# Sheet1.net
KiCad netlist of a schematic drawn in Altium Designer
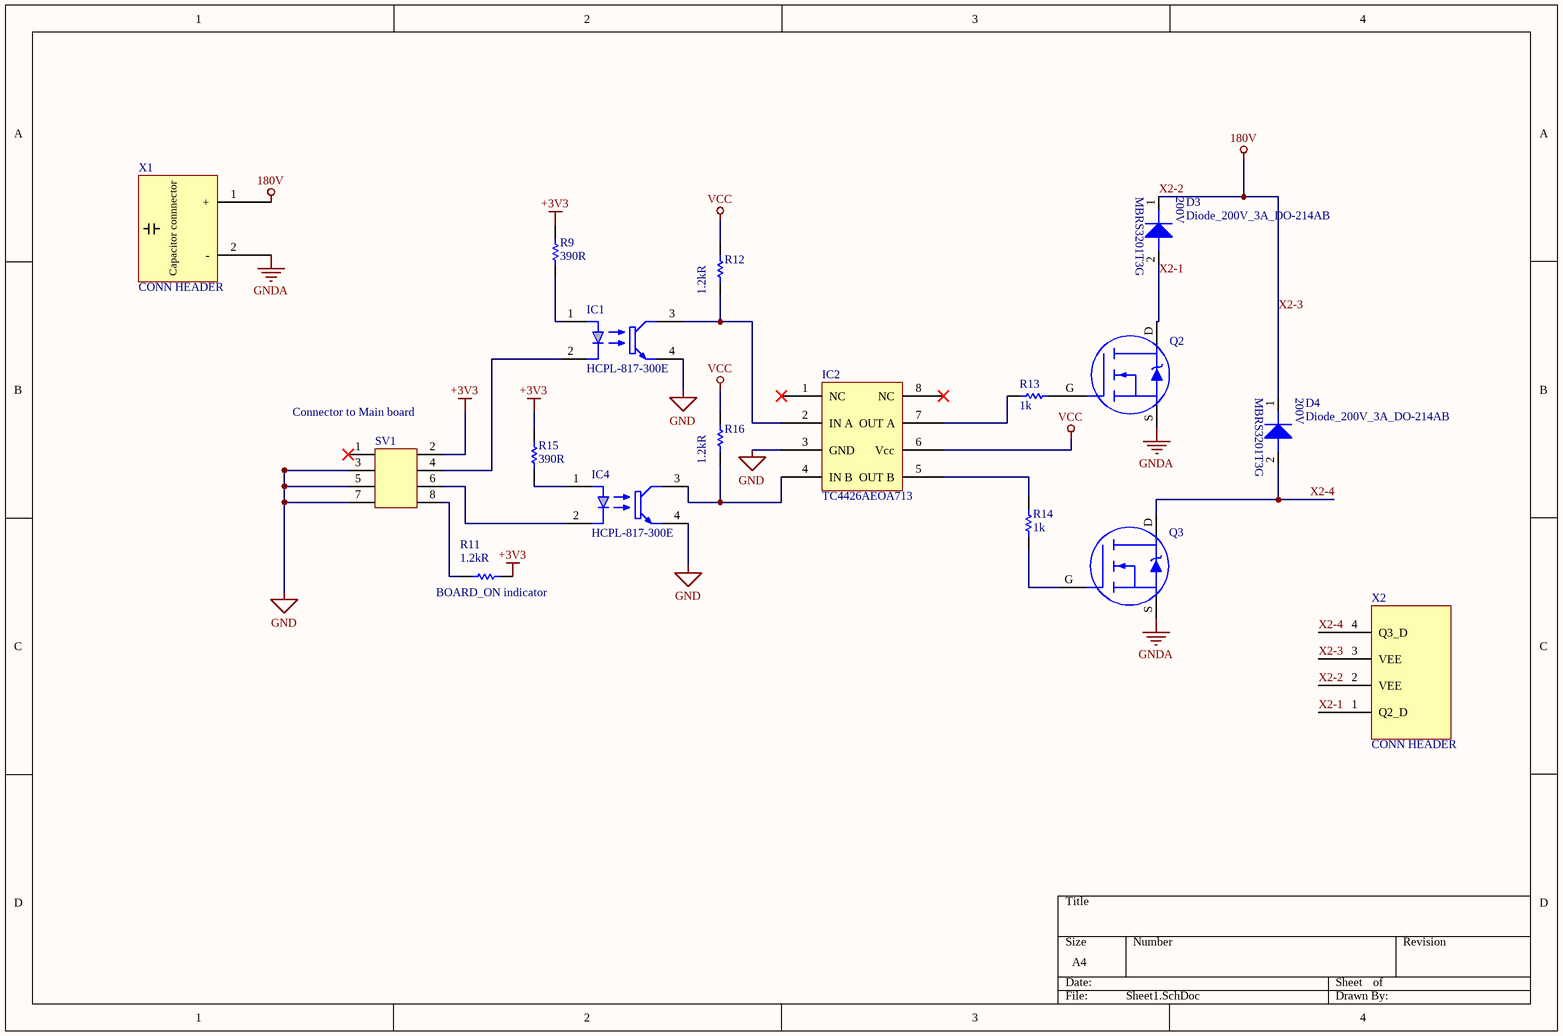
[diagram p0: Sheet1.SchDoc]

(export (version "E")
  (design (tool "Eeschema 10.0.6"))
  (components
    (comp (ref "D3")
      (value "Diode_200V_3A_DO-214AB")
      (footprint "D320")
      (fields
        (field (name "MANUFACTURER") "ON Semiconductor")
        (field (name "MANUFACTURER PART NUMBER") "MBRS3201T3G")
      )
      (libsource (lib "Schlib1") (part "Diode_200V_3A_DO-214AB"))
    )
    (comp (ref "D4")
      (value "Diode_200V_3A_DO-214AB")
      (footprint "D320")
      (fields
        (field (name "MANUFACTURER") "ON Semiconductor")
        (field (name "MANUFACTURER PART NUMBER") "MBRS3201T3G")
      )
      (libsource (lib "Schlib1") (part "Diode_200V_3A_DO-214AB"))
    )
    (comp (ref "IC1")
      (value "HCPL-817-300E")
      (footprint "OPTOISOLATOR_5KV_TRANSISTOR_4SMD")
      (description "OPTOISOLATOR 5KV TRANSISTOR 4SMD")
      (fields (field (name "MANUFACTURER") "Broadcom Avago"))
      (libsource (lib "Phototransistor(Optocoupler)") (part "HCPL-817-300E"))
    )
    (comp (ref "IC2")
      (value "TC4426AEOA713")
      (footprint "CI Driver")
      (description "MOSFET DRVR 1.5A 2-OUT Lo Side Inv 8-Pin SOIC N T/R")
      (fields (field (name "MANUFACTURER") "Microchip"))
      (libsource (lib "Drivers") (part "TC4426AEOA713"))
    )
    (comp (ref "IC4")
      (value "HCPL-817-300E")
      (footprint "OPTOISOLATOR_5KV_TRANSISTOR_4SMD")
      (description "OPTOISOLATOR 5KV TRANSISTOR 4SMD")
      (fields (field (name "MANUFACTURER") "Broadcom Avago"))
      (libsource (lib "Phototransistor(Optocoupler)") (part "HCPL-817-300E"))
    )
    (comp (ref "Q2")
      (value "IRFSL4127PBF")
      (footprint "TO-262")
      (description "200V Single N-Channel HEXFET Power MOSFET Switch in a TO-262 package")
      (fields (field (name "MANUFACTURER") "Infineon"))
      (libsource (lib "Transistors") (part "IRFSL4127PBF"))
    )
    (comp (ref "Q3")
      (value "IRFSL4127PBF")
      (footprint "TO-262")
      (description "200V Single N-Channel HEXFET Power MOSFET Switch in a TO-262 package")
      (fields (field (name "MANUFACTURER") "Infineon"))
      (libsource (lib "Transistors") (part "IRFSL4127PBF"))
    )
    (comp (ref "R9")
      (value "390R")
      (footprint "Resistor_0805")
      (description "RES SMD 0805 390R 5% 1/8W")
      (fields (field (name "TOLERANCE") "1%"))
      (libsource (lib "Resistors") (part "Res_390R_0805"))
    )
    (comp (ref "R11")
      (value "Res_1.2K_0805_1%")
      (footprint "0805")
      (description "PANASONIC ELECTRONIC COMPONENTS - ERJ6ENF1201V - RES, THICK FILM, 1K2, 125MW, 1%, REEL")
      (fields
        (field (name "MANUFACTURER") "Panasonic")
        (field (name "MANUFACTURER PART NUMBER") "ERJ-6ENF1201V")
      )
      (libsource (lib "Resistors") (part "Res_1.2K_0805_1%"))
    )
    (comp (ref "R12")
      (value "Res_1.2K_0805_1%")
      (footprint "0805")
      (description "PANASONIC ELECTRONIC COMPONENTS - ERJ6ENF1201V - RES, THICK FILM, 1K2, 125MW, 1%, REEL")
      (fields
        (field (name "MANUFACTURER") "Panasonic")
        (field (name "MANUFACTURER PART NUMBER") "ERJ-6ENF1201V")
      )
      (libsource (lib "Resistors") (part "Res_1.2K_0805_1%"))
    )
    (comp (ref "R13")
      (value "1k")
      (footprint "Resistor_0805")
      (description "RES SMD 0805 1k 1/8W")
      (libsource (lib "Resistors") (part "Res_1k_0805"))
    )
    (comp (ref "R14")
      (value "1k")
      (footprint "Resistor_0805")
      (description "RES SMD 0805 1k 1/8W")
      (libsource (lib "Resistors") (part "Res_1k_0805"))
    )
    (comp (ref "R15")
      (value "390R")
      (footprint "Resistor_0805")
      (description "RES SMD 0805 390R 5% 1/8W")
      (fields (field (name "TOLERANCE") "1%"))
      (libsource (lib "Resistors") (part "Res_390R_0805"))
    )
    (comp (ref "R16")
      (value "Res_1.2K_0805_1%")
      (footprint "0805")
      (description "PANASONIC ELECTRONIC COMPONENTS - ERJ6ENF1201V - RES, THICK FILM, 1K2, 125MW, 1%, REEL")
      (fields
        (field (name "MANUFACTURER") "Panasonic")
        (field (name "MANUFACTURER PART NUMBER") "ERJ-6ENF1201V")
      )
      (libsource (lib "Resistors") (part "Res_1.2K_0805_1%"))
    )
    (comp (ref "SV1")
      (value "90131-0764")
      (footprint "CONN HEADER VERT 8POS 2.54MM")
      (description "Conn Unshrouded Header HDR 8 POS 2.54mm Solder ST Thru-Hole Tray")
      (fields (field (name "MANUFACTURER") "Molex"))
      (libsource (lib "Conectors_Molex") (part "90131-0764"))
    )
    (comp (ref "X1")
      (value "CONN HEADER")
      (footprint "CONN HEADER R_A 2POS 3.98MM")
      (description "Conn Wire to Board HDR 2 POS 3.96mm Solder RA Thru-Hole KK® Bag")
      (libsource (lib "kicker_andrei") (part "CONN HEADER R_A 2POS 3.96MM"))
    )
    (comp (ref "X2")
      (value "CONN HEADER")
      (footprint "CONN HEADER R_A 4POS 3.98MM")
      (description "Headers & Wire Housings R/A PCB HDR 4P TIN FRICTION LOCK")
      (libsource (lib "kicker_andrei") (part "CONN HEADER R_A 4POS 3.96MM"))
    )
  )
  (nets
    (net (code "1") (name "+3V3") (class "Default")
      (node (ref "R11") (pin "2") (pinfunction "2_2") (pintype "passive"))
      (node (ref "R15") (pin "2") (pinfunction "2_2") (pintype "passive"))
      (node (ref "R9") (pin "2") (pinfunction "2_2") (pintype "passive"))
      (node (ref "SV1") (pin "2") (pinfunction "2_2") (pintype "passive"))
    )
    (net (code "2") (name "/X2-1") (class "Default")
      (node (ref "D3") (pin "2") (pinfunction "2_2") (pintype "passive"))
      (node (ref "Q2") (pin "D") (pinfunction "D_D") (pintype "passive"))
      (node (ref "X2") (pin "1") (pinfunction "Q2_D_1") (pintype "passive"))
    )
    (net (code "3") (name "/X2-4") (class "Default")
      (node (ref "D4") (pin "2") (pinfunction "2_2") (pintype "passive"))
      (node (ref "Q3") (pin "D") (pinfunction "D_D") (pintype "passive"))
      (node (ref "X2") (pin "4") (pinfunction "Q3_D_4") (pintype "passive"))
    )
    (net (code "4") (name "180V") (class "Default")
      (node (ref "D3") (pin "1") (pinfunction "1_1") (pintype "passive"))
      (node (ref "D4") (pin "1") (pinfunction "1_1") (pintype "passive"))
      (node (ref "X1") (pin "1") (pinfunction "+_1") (pintype "passive"))
      (node (ref "X2") (pin "2") (pinfunction "VEE_2") (pintype "passive"))
      (node (ref "X2") (pin "3") (pinfunction "VEE_3") (pintype "passive"))
    )
    (net (code "5") (name "GND") (class "Default")
      (node (ref "IC1") (pin "4") (pinfunction "Emitter_4") (pintype "passive"))
      (node (ref "IC2") (pin "3") (pinfunction "GND_3") (pintype "passive"))
      (node (ref "IC4") (pin "4") (pinfunction "Emitter_4") (pintype "passive"))
      (node (ref "SV1") (pin "3") (pinfunction "3_3") (pintype "passive"))
      (node (ref "SV1") (pin "5") (pinfunction "5_5") (pintype "passive"))
      (node (ref "SV1") (pin "7") (pinfunction "7_7") (pintype "passive"))
    )
    (net (code "6") (name "GNDA") (class "Default")
      (node (ref "Q2") (pin "S") (pinfunction "S_S") (pintype "passive"))
      (node (ref "Q3") (pin "S") (pinfunction "S_S") (pintype "passive"))
      (node (ref "X1") (pin "2") (pinfunction "-_2") (pintype "passive"))
    )
    (net (code "7") (name "Net-(IC1-Anode)") (class "Default")
      (node (ref "IC1") (pin "1") (pinfunction "Anode_1") (pintype "passive"))
      (node (ref "R9") (pin "1") (pinfunction "1_1") (pintype "passive"))
    )
    (net (code "8") (name "Net-(IC1-Cathode)") (class "Default")
      (node (ref "IC1") (pin "2") (pinfunction "Cathode_2") (pintype "passive"))
      (node (ref "SV1") (pin "4") (pinfunction "4_4") (pintype "passive"))
    )
    (net (code "9") (name "Net-(IC1-Collector)") (class "Default")
      (node (ref "IC1") (pin "3") (pinfunction "Collector_3") (pintype "passive"))
      (node (ref "IC2") (pin "2") (pinfunction "IN_A_2") (pintype "passive"))
      (node (ref "R12") (pin "1") (pinfunction "1_1") (pintype "passive"))
    )
    (net (code "10") (name "Net-(IC2-IN_B)") (class "Default")
      (node (ref "IC2") (pin "4") (pinfunction "IN_B_4") (pintype "passive"))
      (node (ref "IC4") (pin "3") (pinfunction "Collector_3") (pintype "passive"))
      (node (ref "R16") (pin "1") (pinfunction "1_1") (pintype "passive"))
    )
    (net (code "11") (name "Net-(IC2-OUT_A)") (class "Default")
      (node (ref "IC2") (pin "7") (pinfunction "OUT_A_7") (pintype "passive"))
      (node (ref "R13") (pin "1") (pinfunction "1_1") (pintype "passive"))
    )
    (net (code "12") (name "Net-(IC2-OUT_B)") (class "Default")
      (node (ref "IC2") (pin "5") (pinfunction "OUT_B_5") (pintype "passive"))
      (node (ref "R14") (pin "2") (pinfunction "2_2") (pintype "passive"))
    )
    (net (code "13") (name "Net-(IC4-Anode)") (class "Default")
      (node (ref "IC4") (pin "1") (pinfunction "Anode_1") (pintype "passive"))
      (node (ref "R15") (pin "1") (pinfunction "1_1") (pintype "passive"))
    )
    (net (code "14") (name "Net-(IC4-Cathode)") (class "Default")
      (node (ref "IC4") (pin "2") (pinfunction "Cathode_2") (pintype "passive"))
      (node (ref "SV1") (pin "6") (pinfunction "6_6") (pintype "passive"))
    )
    (net (code "15") (name "Net-(Q2-PadG)") (class "Default")
      (node (ref "Q2") (pin "G") (pinfunction "G_G") (pintype "passive"))
      (node (ref "R13") (pin "2") (pinfunction "2_2") (pintype "passive"))
    )
    (net (code "16") (name "Net-(Q3-PadG)") (class "Default")
      (node (ref "Q3") (pin "G") (pinfunction "G_G") (pintype "passive"))
      (node (ref "R14") (pin "1") (pinfunction "1_1") (pintype "passive"))
    )
    (net (code "17") (name "Net-(R11-Pad1)") (class "Default")
      (node (ref "R11") (pin "1") (pinfunction "1_1") (pintype "passive"))
      (node (ref "SV1") (pin "8") (pinfunction "8_8") (pintype "passive"))
    )
    (net (code "18") (name "VCC") (class "Default")
      (node (ref "IC2") (pin "6") (pinfunction "Vcc_6") (pintype "passive"))
      (node (ref "R12") (pin "2") (pinfunction "2_2") (pintype "passive"))
      (node (ref "R16") (pin "2") (pinfunction "2_2") (pintype "passive"))
    )
    (net (code "19") (name "unconnected-(IC2-NC-Pad1)") (class "Default")
      (node (ref "IC2") (pin "1") (pinfunction "NC_1") (pintype "passive+no_connect"))
    )
    (net (code "20") (name "unconnected-(IC2-NC-Pad8)") (class "Default")
      (node (ref "IC2") (pin "8") (pinfunction "NC_8") (pintype "passive+no_connect"))
    )
    (net (code "21") (name "unconnected-(SV1-Pad1)") (class "Default")
      (node (ref "SV1") (pin "1") (pinfunction "1_1") (pintype "passive+no_connect"))
    )
  )
)
